# Scheme.net
KiCad netlist of a schematic drawn in Altium Designer
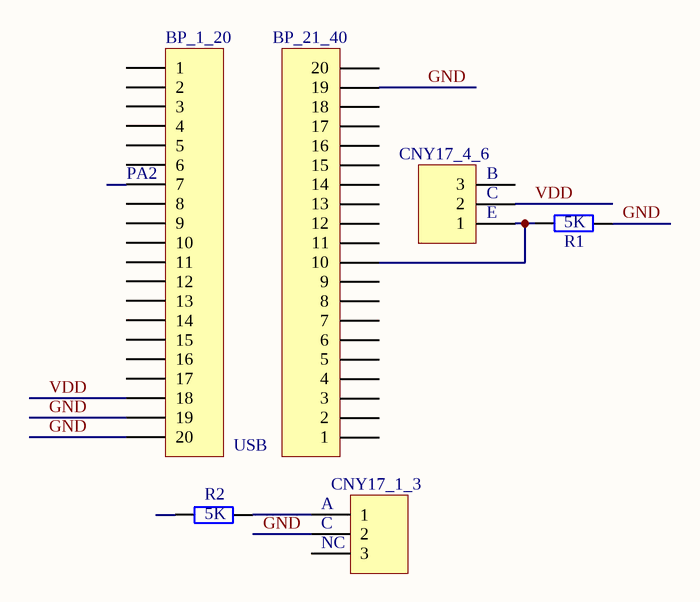
[diagram p0: Scheme.SchDoc]

(export (version "E")
  (design (tool "Eeschema 10.0.6"))
  (components
    (comp (ref "BP_1_20")
      (value "Header 20")
      (footprint "HDR1X20")
      (description "Header, 20-Pin")
      (fields (field (name "PUBLISHER") "Altium Limited"))
      (libsource (lib "") (part "Header 20_1"))
    )
    (comp (ref "BP_21_40")
      (value "Header 20")
      (footprint "HDR1X20")
      (description "Header, 20-Pin")
      (fields (field (name "PUBLISHER") "Altium Limited"))
      (libsource (lib "Miscellaneous Connectors") (part "Header 20"))
    )
    (comp (ref "CNY17_1_3")
      (value "Header 3")
      (footprint "HDR1X3")
      (description "Header, 3-Pin")
      (fields (field (name "PUBLISHER") "Altium Limited"))
      (libsource (lib "") (part "Header 3_1"))
    )
    (comp (ref "CNY17_4_6")
      (value "Header 3")
      (footprint "HDR1X3")
      (description "Header, 3-Pin")
      (fields (field (name "PUBLISHER") "Altium Limited"))
      (libsource (lib "Miscellaneous Connectors") (part "Header 3"))
    )
    (comp (ref "R1")
      (value "5K")
      (footprint "AXIAL-0.4")
      (description "Resistor")
      (fields (field (name "Comment") "5k") (field (name "PUBLISHER") "Altium Limited"))
      (libsource (lib "Miscellaneous Devices") (part "Res2"))
    )
    (comp (ref "R2")
      (value "5K")
      (footprint "AXIAL-0.4")
      (description "Resistor")
      (fields (field (name "Comment") "5k") (field (name "PUBLISHER") "Altium Limited"))
      (libsource (lib "Miscellaneous Devices") (part "Res2"))
    )
  )
  (nets
    (net (code "1") (name "/GND") (class "Default")
      (node (ref "BP_1_20") (pin "19") (pinfunction "19_19") (pintype "passive"))
      (node (ref "BP_1_20") (pin "20") (pinfunction "20_20") (pintype "passive"))
      (node (ref "BP_21_40") (pin "19") (pinfunction "19_19") (pintype "passive"))
      (node (ref "CNY17_1_3") (pin "2") (pinfunction "2_2") (pintype "passive"))
      (node (ref "R1") (pin "2") (pinfunction "2_2") (pintype "passive"))
    )
    (net (code "2") (name "/VDD") (class "Default")
      (node (ref "BP_1_20") (pin "18") (pinfunction "18_18") (pintype "passive"))
      (node (ref "CNY17_4_6") (pin "2") (pinfunction "2_2") (pintype "passive"))
    )
    (net (code "3") (name "Net-(BP_21_40-Pad10)") (class "Default")
      (node (ref "BP_21_40") (pin "10") (pinfunction "10_10") (pintype "passive"))
      (node (ref "CNY17_4_6") (pin "1") (pinfunction "1_1") (pintype "passive"))
      (node (ref "R1") (pin "1") (pinfunction "1_1") (pintype "passive"))
    )
    (net (code "4") (name "Net-(CNY17_1_3-Pad1)") (class "Default")
      (node (ref "CNY17_1_3") (pin "1") (pinfunction "1_1") (pintype "passive"))
      (node (ref "R2") (pin "2") (pinfunction "2_2") (pintype "passive"))
    )
    (net (code "5") (name "unconnected-(BP_1_20-Pad1)") (class "Default")
      (node (ref "BP_1_20") (pin "1") (pinfunction "1_1") (pintype "passive"))
    )
    (net (code "6") (name "unconnected-(BP_1_20-Pad2)") (class "Default")
      (node (ref "BP_1_20") (pin "2") (pinfunction "2_2") (pintype "passive"))
    )
    (net (code "7") (name "unconnected-(BP_1_20-Pad3)") (class "Default")
      (node (ref "BP_1_20") (pin "3") (pinfunction "3_3") (pintype "passive"))
    )
    (net (code "8") (name "unconnected-(BP_1_20-Pad4)") (class "Default")
      (node (ref "BP_1_20") (pin "4") (pinfunction "4_4") (pintype "passive"))
    )
    (net (code "9") (name "unconnected-(BP_1_20-Pad5)") (class "Default")
      (node (ref "BP_1_20") (pin "5") (pinfunction "5_5") (pintype "passive"))
    )
    (net (code "10") (name "unconnected-(BP_1_20-Pad6)") (class "Default")
      (node (ref "BP_1_20") (pin "6") (pinfunction "6_6") (pintype "passive"))
    )
    (net (code "11") (name "unconnected-(BP_1_20-Pad7)") (class "Default")
      (node (ref "BP_1_20") (pin "7") (pinfunction "7_7") (pintype "passive"))
    )
    (net (code "12") (name "unconnected-(BP_1_20-Pad8)") (class "Default")
      (node (ref "BP_1_20") (pin "8") (pinfunction "8_8") (pintype "passive"))
    )
    (net (code "13") (name "unconnected-(BP_1_20-Pad9)") (class "Default")
      (node (ref "BP_1_20") (pin "9") (pinfunction "9_9") (pintype "passive"))
    )
    (net (code "14") (name "unconnected-(BP_1_20-Pad10)") (class "Default")
      (node (ref "BP_1_20") (pin "10") (pinfunction "10_10") (pintype "passive"))
    )
    (net (code "15") (name "unconnected-(BP_1_20-Pad11)") (class "Default")
      (node (ref "BP_1_20") (pin "11") (pinfunction "11_11") (pintype "passive"))
    )
    (net (code "16") (name "unconnected-(BP_1_20-Pad12)") (class "Default")
      (node (ref "BP_1_20") (pin "12") (pinfunction "12_12") (pintype "passive"))
    )
    (net (code "17") (name "unconnected-(BP_1_20-Pad13)") (class "Default")
      (node (ref "BP_1_20") (pin "13") (pinfunction "13_13") (pintype "passive"))
    )
    (net (code "18") (name "unconnected-(BP_1_20-Pad14)") (class "Default")
      (node (ref "BP_1_20") (pin "14") (pinfunction "14_14") (pintype "passive"))
    )
    (net (code "19") (name "unconnected-(BP_1_20-Pad15)") (class "Default")
      (node (ref "BP_1_20") (pin "15") (pinfunction "15_15") (pintype "passive"))
    )
    (net (code "20") (name "unconnected-(BP_1_20-Pad16)") (class "Default")
      (node (ref "BP_1_20") (pin "16") (pinfunction "16_16") (pintype "passive"))
    )
    (net (code "21") (name "unconnected-(BP_1_20-Pad17)") (class "Default")
      (node (ref "BP_1_20") (pin "17") (pinfunction "17_17") (pintype "passive"))
    )
    (net (code "22") (name "unconnected-(BP_21_40-Pad1)") (class "Default")
      (node (ref "BP_21_40") (pin "1") (pinfunction "1_1") (pintype "passive"))
    )
    (net (code "23") (name "unconnected-(BP_21_40-Pad2)") (class "Default")
      (node (ref "BP_21_40") (pin "2") (pinfunction "2_2") (pintype "passive"))
    )
    (net (code "24") (name "unconnected-(BP_21_40-Pad3)") (class "Default")
      (node (ref "BP_21_40") (pin "3") (pinfunction "3_3") (pintype "passive"))
    )
    (net (code "25") (name "unconnected-(BP_21_40-Pad4)") (class "Default")
      (node (ref "BP_21_40") (pin "4") (pinfunction "4_4") (pintype "passive"))
    )
    (net (code "26") (name "unconnected-(BP_21_40-Pad5)") (class "Default")
      (node (ref "BP_21_40") (pin "5") (pinfunction "5_5") (pintype "passive"))
    )
    (net (code "27") (name "unconnected-(BP_21_40-Pad6)") (class "Default")
      (node (ref "BP_21_40") (pin "6") (pinfunction "6_6") (pintype "passive"))
    )
    (net (code "28") (name "unconnected-(BP_21_40-Pad7)") (class "Default")
      (node (ref "BP_21_40") (pin "7") (pinfunction "7_7") (pintype "passive"))
    )
    (net (code "29") (name "unconnected-(BP_21_40-Pad8)") (class "Default")
      (node (ref "BP_21_40") (pin "8") (pinfunction "8_8") (pintype "passive"))
    )
    (net (code "30") (name "unconnected-(BP_21_40-Pad9)") (class "Default")
      (node (ref "BP_21_40") (pin "9") (pinfunction "9_9") (pintype "passive"))
    )
    (net (code "31") (name "unconnected-(BP_21_40-Pad11)") (class "Default")
      (node (ref "BP_21_40") (pin "11") (pinfunction "11_11") (pintype "passive"))
    )
    (net (code "32") (name "unconnected-(BP_21_40-Pad12)") (class "Default")
      (node (ref "BP_21_40") (pin "12") (pinfunction "12_12") (pintype "passive"))
    )
    (net (code "33") (name "unconnected-(BP_21_40-Pad13)") (class "Default")
      (node (ref "BP_21_40") (pin "13") (pinfunction "13_13") (pintype "passive"))
    )
    (net (code "34") (name "unconnected-(BP_21_40-Pad14)") (class "Default")
      (node (ref "BP_21_40") (pin "14") (pinfunction "14_14") (pintype "passive"))
    )
    (net (code "35") (name "unconnected-(BP_21_40-Pad15)") (class "Default")
      (node (ref "BP_21_40") (pin "15") (pinfunction "15_15") (pintype "passive"))
    )
    (net (code "36") (name "unconnected-(BP_21_40-Pad16)") (class "Default")
      (node (ref "BP_21_40") (pin "16") (pinfunction "16_16") (pintype "passive"))
    )
    (net (code "37") (name "unconnected-(BP_21_40-Pad17)") (class "Default")
      (node (ref "BP_21_40") (pin "17") (pinfunction "17_17") (pintype "passive"))
    )
    (net (code "38") (name "unconnected-(BP_21_40-Pad18)") (class "Default")
      (node (ref "BP_21_40") (pin "18") (pinfunction "18_18") (pintype "passive"))
    )
    (net (code "39") (name "unconnected-(BP_21_40-Pad20)") (class "Default")
      (node (ref "BP_21_40") (pin "20") (pinfunction "20_20") (pintype "passive"))
    )
    (net (code "40") (name "unconnected-(CNY17_1_3-Pad3)") (class "Default")
      (node (ref "CNY17_1_3") (pin "3") (pinfunction "3_3") (pintype "passive"))
    )
    (net (code "41") (name "unconnected-(CNY17_4_6-Pad3)") (class "Default")
      (node (ref "CNY17_4_6") (pin "3") (pinfunction "3_3") (pintype "passive"))
    )
    (net (code "42") (name "unconnected-(R2-Pad1)") (class "Default")
      (node (ref "R2") (pin "1") (pinfunction "1_1") (pintype "passive"))
    )
  )
)
